# PingPong_388_2019_rev5.net
KiCad netlist of a schematic drawn in EAGLE
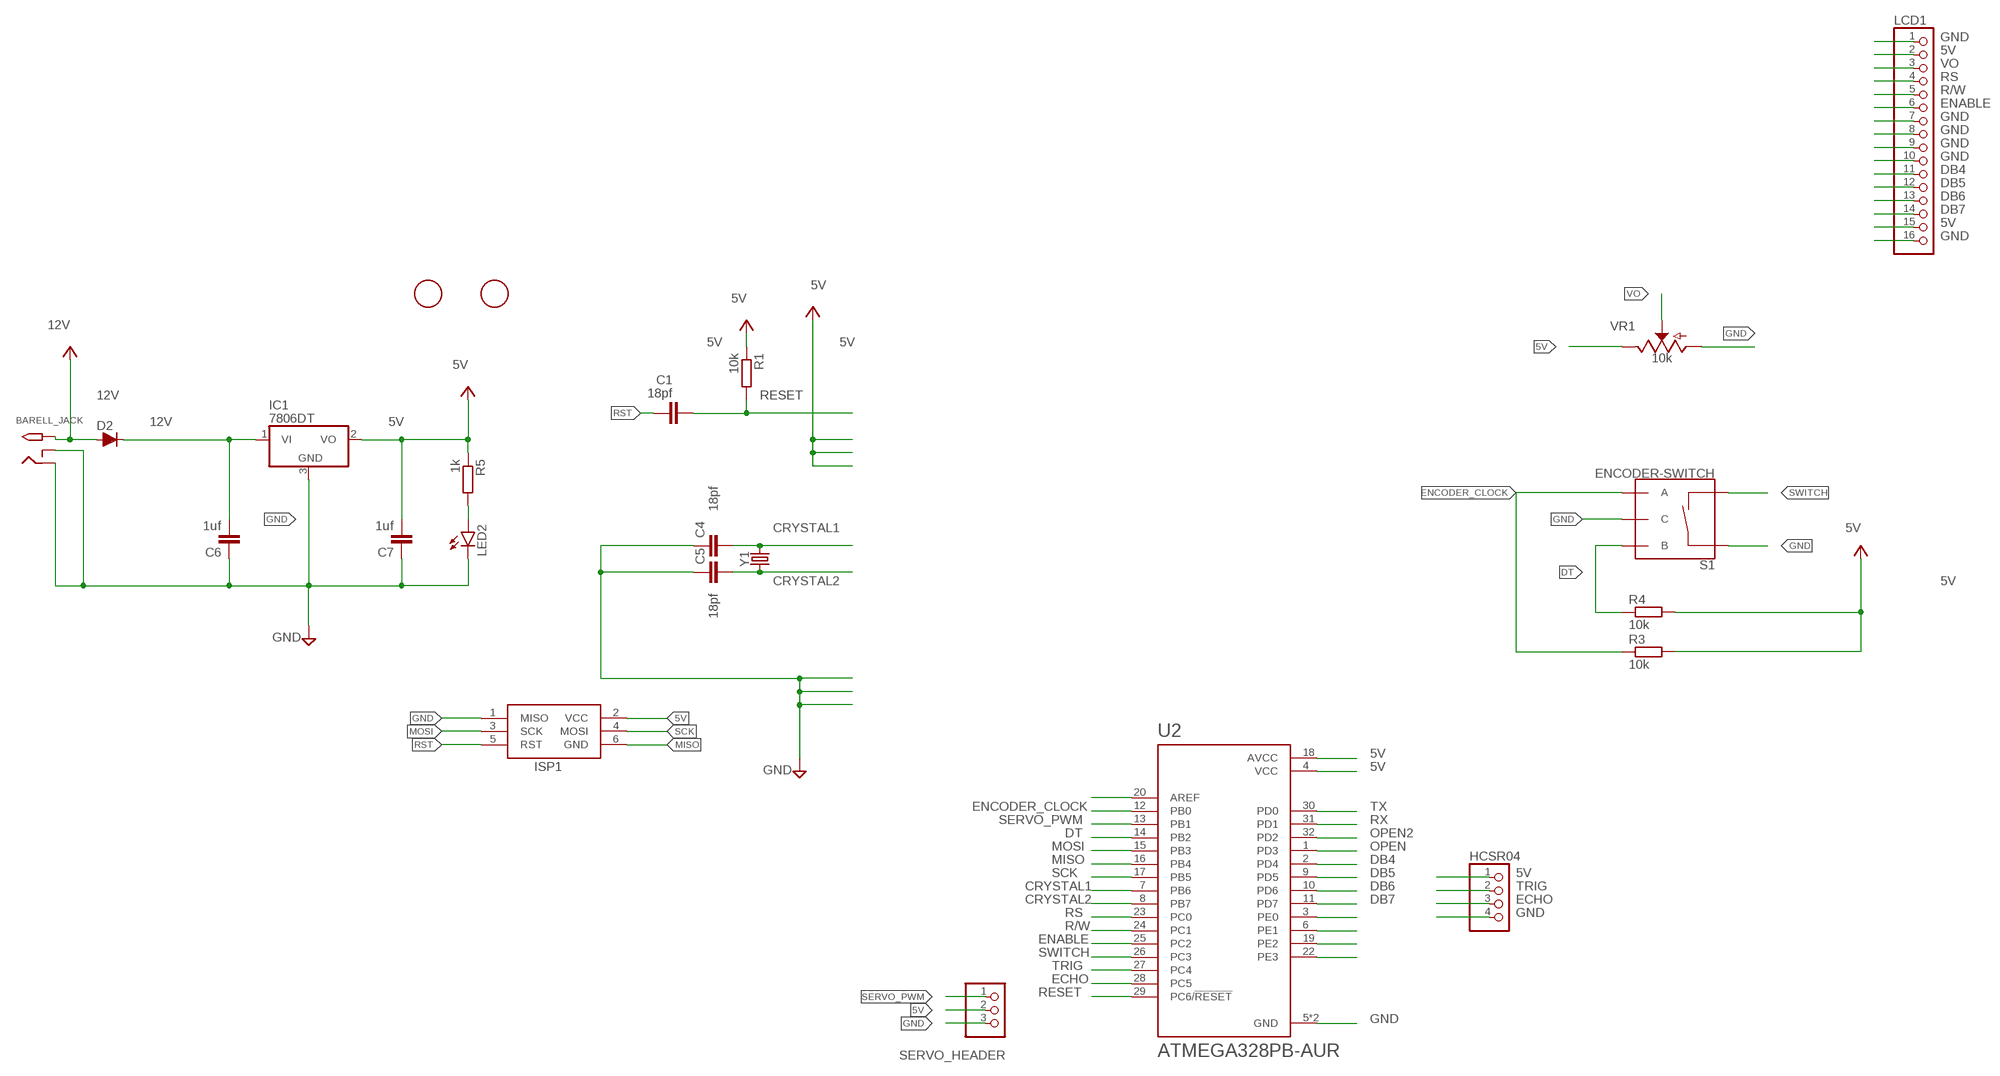
[diagram p0: schematic, sheet 1]

(export (version "E")
  (design (tool "Eeschema 10.0.6"))
  (components
    (comp (ref "BARELL_JACK")
      (value "2.1MMJACKTHM")
      (footprint "eagle-import:PJ-102A")
      (libsource (lib "eagle-import") (part "2.1MMJACKTHM"))
    )
    (comp (ref "C1")
      (value "18pf")
      (footprint "eagle-import:C0805")
      (libsource (lib "eagle-import") (part "C-EUC0805"))
    )
    (comp (ref "C4")
      (value "18pf")
      (footprint "eagle-import:C0805")
      (libsource (lib "eagle-import") (part "C-EUC0805"))
    )
    (comp (ref "C5")
      (value "18pf")
      (footprint "eagle-import:C0805")
      (libsource (lib "eagle-import") (part "C-EUC0805"))
    )
    (comp (ref "C6")
      (value "1uf")
      (footprint "eagle-import:C0805")
      (libsource (lib "eagle-import") (part "C-EUC0805"))
    )
    (comp (ref "C7")
      (value "1uf")
      (footprint "eagle-import:C0805")
      (libsource (lib "eagle-import") (part "C-EUC0805"))
    )
    (comp (ref "D2")
      (value "D-FILL-MLL-34")
      (footprint "eagle-import:MELF-MLL34")
      (libsource (lib "eagle-import") (part "D-FILL-MLL-34"))
    )
    (comp (ref "HCSR04")
      (value "PINHD-1X4")
      (footprint "eagle-import:1X04")
      (libsource (lib "eagle-import") (part "PINHD-1X4"))
    )
    (comp (ref "IC1")
      (value "7806DT")
      (footprint "eagle-import:TO252")
      (libsource (lib "eagle-import") (part "78DT06"))
    )
    (comp (ref "ISP1")
      (value "AVRISP-6")
      (footprint "eagle-import:AVRISP")
      (libsource (lib "eagle-import") (part "AVRISP-6"))
    )
    (comp (ref "LCD1")
      (value "PINHD-1X16")
      (footprint "eagle-import:1X16")
      (libsource (lib "eagle-import") (part "PINHD-1X16"))
    )
    (comp (ref "LED2")
      (value "LEDSML0805")
      (footprint "eagle-import:SML0805")
      (libsource (lib "eagle-import") (part "LEDSML0805"))
    )
    (comp (ref "R1")
      (value "10k")
      (footprint "eagle-import:R0805")
      (libsource (lib "eagle-import") (part "R-EU_R0805"))
    )
    (comp (ref "R3")
      (value "10k")
      (footprint "eagle-import:R0805")
      (libsource (lib "eagle-import") (part "R-EU_R0805"))
    )
    (comp (ref "R4")
      (value "10k")
      (footprint "eagle-import:R0805")
      (libsource (lib "eagle-import") (part "R-EU_R0805"))
    )
    (comp (ref "R5")
      (value "1k")
      (footprint "eagle-import:R0805")
      (libsource (lib "eagle-import") (part "R-EU_R0805"))
    )
    (comp (ref "S1")
      (value "ENCODER-SWITCH")
      (footprint "eagle-import:ROTARY_ENC_PLAIN")
      (libsource (lib "eagle-import") (part "ENCODER-SWITCH"))
    )
    (comp (ref "SERVO_HEADER")
      (value "PINHD-1X3")
      (footprint "eagle-import:1X03")
      (libsource (lib "eagle-import") (part "PINHD-1X3"))
    )
    (comp (ref "U$3")
      (value "FIDUCIAL")
      (footprint "eagle-import:FIDUCIAL_1MM")
      (libsource (lib "eagle-import") (part "FIDUCIAL"))
    )
    (comp (ref "U$4")
      (value "FIDUCIAL")
      (footprint "eagle-import:FIDUCIAL_1MM")
      (libsource (lib "eagle-import") (part "FIDUCIAL"))
    )
    (comp (ref "U2")
      (value "ATMEGA328PB-AUR")
      (footprint "eagle-import:QFP80P900X900X120-32N")
      (fields (field (name "MF") "Microchip"))
      (libsource (lib "eagle-import") (part "ATMEGA328PB-AUR"))
    )
    (comp (ref "VR1")
      (value "10k")
      (footprint "eagle-import:POT-PTH-ALPS")
      (libsource (lib "eagle-import") (part "POTENTIOMETER-PTH-9MM-1/20W-20%"))
    )
    (comp (ref "Y1")
      (value "CRYSTALSMD-HC49UP")
      (footprint "eagle-import:HC49UP")
      (libsource (lib "eagle-import") (part "CRYSTALSMD-HC49UP"))
    )
  )
  (nets
    (net (code "1") (name "/CRYSTAL1") (class "Default")
      (node (ref "C4") (pin "2") (pinfunction "2_2") (pintype "passive"))
      (node (ref "U2") (pin "7") (pinfunction "PB6_7") (pintype "bidirectional"))
      (node (ref "Y1") (pin "2") (pinfunction "2_2") (pintype "passive"))
    )
    (net (code "2") (name "/CRYSTAL2") (class "Default")
      (node (ref "C5") (pin "2") (pinfunction "2_2") (pintype "passive"))
      (node (ref "U2") (pin "8") (pinfunction "PB7_8") (pintype "bidirectional"))
      (node (ref "Y1") (pin "1") (pinfunction "1_1") (pintype "passive"))
    )
    (net (code "3") (name "/DB4") (class "Default")
      (node (ref "LCD1") (pin "11") (pinfunction "11_11") (pintype "passive"))
      (node (ref "U2") (pin "2") (pinfunction "PD4_2") (pintype "bidirectional"))
    )
    (net (code "4") (name "/DB5") (class "Default")
      (node (ref "LCD1") (pin "12") (pinfunction "12_12") (pintype "passive"))
      (node (ref "U2") (pin "9") (pinfunction "PD5_9") (pintype "bidirectional"))
    )
    (net (code "5") (name "/DB6") (class "Default")
      (node (ref "LCD1") (pin "13") (pinfunction "13_13") (pintype "passive"))
      (node (ref "U2") (pin "10") (pinfunction "PD6_10") (pintype "bidirectional"))
    )
    (net (code "6") (name "/DB7") (class "Default")
      (node (ref "LCD1") (pin "14") (pinfunction "14_14") (pintype "passive"))
      (node (ref "U2") (pin "11") (pinfunction "PD7_11") (pintype "bidirectional"))
    )
    (net (code "7") (name "/ECHO") (class "Default")
      (node (ref "HCSR04") (pin "3") (pinfunction "3_3") (pintype "passive"))
      (node (ref "U2") (pin "28") (pinfunction "PC5_28") (pintype "bidirectional"))
    )
    (net (code "8") (name "/ENABLE") (class "Default")
      (node (ref "LCD1") (pin "6") (pinfunction "6_6") (pintype "passive"))
      (node (ref "U2") (pin "25") (pinfunction "PC2_25") (pintype "bidirectional"))
    )
    (net (code "9") (name "/OPEN") (class "Default")
      (node (ref "U2") (pin "1") (pinfunction "PD3_1") (pintype "bidirectional"))
    )
    (net (code "10") (name "/OPEN2") (class "Default")
      (node (ref "U2") (pin "32") (pinfunction "PD2_32") (pintype "bidirectional"))
    )
    (net (code "11") (name "/RESET") (class "Default")
      (node (ref "C1") (pin "2") (pinfunction "2_2") (pintype "passive"))
      (node (ref "R1") (pin "2") (pinfunction "2_2") (pintype "passive"))
      (node (ref "U2") (pin "29") (pinfunction "PC6/~{RESET}_29") (pintype "bidirectional"))
    )
    (net (code "12") (name "/RS") (class "Default")
      (node (ref "LCD1") (pin "4") (pinfunction "4_4") (pintype "passive"))
      (node (ref "U2") (pin "23") (pinfunction "PC0_23") (pintype "bidirectional"))
    )
    (net (code "13") (name "/RX") (class "Default")
      (node (ref "U2") (pin "31") (pinfunction "PD1_31") (pintype "bidirectional"))
    )
    (net (code "14") (name "/R{slash}W") (class "Default")
      (node (ref "LCD1") (pin "5") (pinfunction "5_5") (pintype "passive"))
      (node (ref "U2") (pin "24") (pinfunction "PC1_24") (pintype "bidirectional"))
    )
    (net (code "15") (name "/TRIG") (class "Default")
      (node (ref "HCSR04") (pin "2") (pinfunction "2_2") (pintype "passive"))
      (node (ref "U2") (pin "27") (pinfunction "PC4_27") (pintype "bidirectional"))
    )
    (net (code "16") (name "/TX") (class "Default")
      (node (ref "U2") (pin "30") (pinfunction "PD0_30") (pintype "bidirectional"))
    )
    (net (code "17") (name "5V") (class "Default")
      (node (ref "C7") (pin "2") (pinfunction "2_2") (pintype "passive"))
      (node (ref "HCSR04") (pin "1") (pinfunction "1_1") (pintype "passive"))
      (node (ref "IC1") (pin "2") (pinfunction "VO_2") (pintype "passive"))
      (node (ref "ISP1") (pin "2") (pinfunction "VCC_2") (pintype "power_in"))
      (node (ref "LCD1") (pin "15") (pinfunction "15_15") (pintype "passive"))
      (node (ref "LCD1") (pin "2") (pinfunction "2_2") (pintype "passive"))
      (node (ref "R1") (pin "1") (pinfunction "1_1") (pintype "passive"))
      (node (ref "R3") (pin "2") (pinfunction "2_2") (pintype "passive"))
      (node (ref "R4") (pin "2") (pinfunction "2_2") (pintype "passive"))
      (node (ref "R5") (pin "1") (pinfunction "1_1") (pintype "passive"))
      (node (ref "SERVO_HEADER") (pin "2") (pinfunction "2_2") (pintype "passive"))
      (node (ref "U2") (pin "18") (pinfunction "AVCC_18") (pintype "power_in"))
      (node (ref "U2") (pin "4") (pinfunction "VCC_4") (pintype "power_in"))
      (node (ref "VR1") (pin "P$1") (pinfunction "E_P$1") (pintype "passive"))
    )
    (net (code "18") (name "12V") (class "Default")
      (node (ref "BARELL_JACK") (pin "TIP") (pinfunction "TIP_TIP") (pintype "bidirectional"))
      (node (ref "C6") (pin "2") (pinfunction "2_2") (pintype "passive"))
      (node (ref "D2") (pin "1") (pinfunction "C_1") (pintype "passive"))
      (node (ref "D2") (pin "2") (pinfunction "A_2") (pintype "passive"))
      (node (ref "IC1") (pin "1") (pinfunction "VI_1") (pintype "input"))
    )
    (net (code "19") (name "DT") (class "Default")
      (node (ref "R4") (pin "1") (pinfunction "1_1") (pintype "passive"))
      (node (ref "S1") (pin "B") (pinfunction "B_B") (pintype "bidirectional"))
      (node (ref "U2") (pin "14") (pinfunction "PB2_14") (pintype "bidirectional"))
    )
    (net (code "20") (name "ENCODER_CLOCK") (class "Default")
      (node (ref "R3") (pin "1") (pinfunction "1_1") (pintype "passive"))
      (node (ref "S1") (pin "A") (pinfunction "A_A") (pintype "bidirectional"))
      (node (ref "U2") (pin "12") (pinfunction "PB0_12") (pintype "bidirectional"))
    )
    (net (code "21") (name "GND") (class "Default")
      (node (ref "BARELL_JACK") (pin "RING") (pinfunction "RING_RING") (pintype "bidirectional"))
      (node (ref "BARELL_JACK") (pin "RING_SW") (pinfunction "RING_SW_RING_SW") (pintype "bidirectional"))
      (node (ref "C4") (pin "1") (pinfunction "1_1") (pintype "passive"))
      (node (ref "C5") (pin "1") (pinfunction "1_1") (pintype "passive"))
      (node (ref "C6") (pin "1") (pinfunction "1_1") (pintype "passive"))
      (node (ref "C7") (pin "1") (pinfunction "1_1") (pintype "passive"))
      (node (ref "HCSR04") (pin "4") (pinfunction "4_4") (pintype "passive"))
      (node (ref "IC1") (pin "3") (pinfunction "GND_3") (pintype "passive"))
      (node (ref "ISP1") (pin "1") (pinfunction "MISO_1") (pintype "input"))
      (node (ref "LCD1") (pin "1") (pinfunction "1_1") (pintype "passive"))
      (node (ref "LCD1") (pin "10") (pinfunction "10_10") (pintype "passive"))
      (node (ref "LCD1") (pin "16") (pinfunction "16_16") (pintype "passive"))
      (node (ref "LCD1") (pin "7") (pinfunction "7_7") (pintype "passive"))
      (node (ref "LCD1") (pin "8") (pinfunction "8_8") (pintype "passive"))
      (node (ref "LCD1") (pin "9") (pinfunction "9_9") (pintype "passive"))
      (node (ref "LED2") (pin "C") (pinfunction "C_C") (pintype "passive"))
      (node (ref "S1") (pin "C") (pinfunction "C_C") (pintype "bidirectional"))
      (node (ref "S1") (pin "SW+") (pinfunction "SW+_SW+") (pintype "bidirectional"))
      (node (ref "SERVO_HEADER") (pin "3") (pinfunction "3_3") (pintype "passive"))
      (node (ref "U2") (pin "21") (pinfunction "GND_21") (pintype "power_in"))
      (node (ref "U2") (pin "5") (pinfunction "GND_5") (pintype "power_in"))
      (node (ref "VR1") (pin "P$3") (pinfunction "A_P$3") (pintype "passive"))
    )
    (net (code "22") (name "MISO") (class "Default")
      (node (ref "ISP1") (pin "6") (pinfunction "GND_6") (pintype "power_in"))
      (node (ref "U2") (pin "16") (pinfunction "PB4_16") (pintype "bidirectional"))
    )
    (net (code "23") (name "MOSI") (class "Default")
      (node (ref "ISP1") (pin "3") (pinfunction "SCK_3") (pintype "output"))
      (node (ref "U2") (pin "15") (pinfunction "PB3_15") (pintype "bidirectional"))
    )
    (net (code "24") (name "Net-(LED2-PadA)") (class "Default")
      (node (ref "LED2") (pin "A") (pinfunction "A_A") (pintype "passive"))
      (node (ref "R5") (pin "2") (pinfunction "2_2") (pintype "passive"))
    )
    (net (code "25") (name "RST") (class "Default")
      (node (ref "C1") (pin "1") (pinfunction "1_1") (pintype "passive"))
      (node (ref "ISP1") (pin "5") (pinfunction "RST_5") (pintype "output"))
    )
    (net (code "26") (name "SCK") (class "Default")
      (node (ref "ISP1") (pin "4") (pinfunction "MOSI_4") (pintype "output"))
      (node (ref "U2") (pin "17") (pinfunction "PB5_17") (pintype "bidirectional"))
    )
    (net (code "27") (name "SERVO_PWM") (class "Default")
      (node (ref "SERVO_HEADER") (pin "1") (pinfunction "1_1") (pintype "passive"))
      (node (ref "U2") (pin "13") (pinfunction "PB1_13") (pintype "bidirectional"))
    )
    (net (code "28") (name "SWITCH") (class "Default")
      (node (ref "S1") (pin "SW-") (pinfunction "SW-_SW-") (pintype "bidirectional"))
      (node (ref "U2") (pin "26") (pinfunction "PC3_26") (pintype "bidirectional"))
    )
    (net (code "29") (name "VO") (class "Default")
      (node (ref "LCD1") (pin "3") (pinfunction "3_3") (pintype "passive"))
      (node (ref "VR1") (pin "P$2") (pinfunction "S_P$2") (pintype "passive"))
    )
    (net (code "30") (name "unconnected-(U2-AREF-Pad20)") (class "Default")
      (node (ref "U2") (pin "20") (pinfunction "AREF_20") (pintype "input"))
    )
    (net (code "31") (name "unconnected-(U2-PE0-Pad3)") (class "Default")
      (node (ref "U2") (pin "3") (pinfunction "PE0_3") (pintype "bidirectional"))
    )
    (net (code "32") (name "unconnected-(U2-PE1-Pad6)") (class "Default")
      (node (ref "U2") (pin "6") (pinfunction "PE1_6") (pintype "bidirectional"))
    )
    (net (code "33") (name "unconnected-(U2-PE2-Pad19)") (class "Default")
      (node (ref "U2") (pin "19") (pinfunction "PE2_19") (pintype "bidirectional"))
    )
    (net (code "34") (name "unconnected-(U2-PE3-Pad22)") (class "Default")
      (node (ref "U2") (pin "22") (pinfunction "PE3_22") (pintype "bidirectional"))
    )
  )
)
